# TGCC-HC-1_RF_Module.net
KiCad netlist of a schematic drawn in Altium Designer
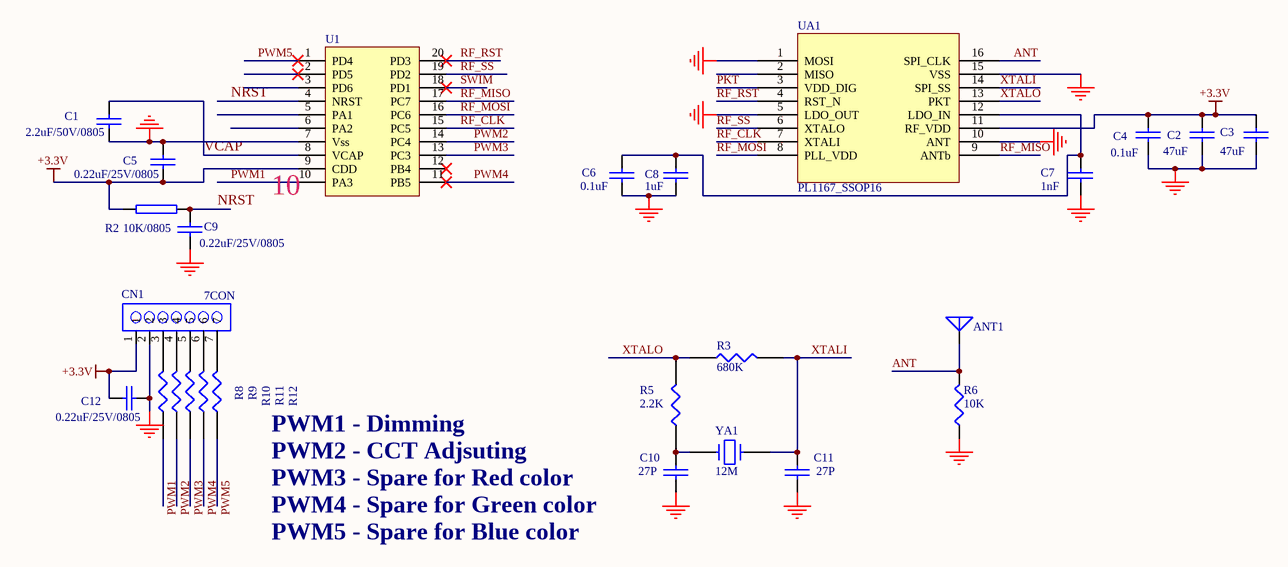
[diagram p0: TGCC-HC-1 RF Module.SchDoc]

(export (version "E")
  (design (tool "Eeschema 10.0.6"))
  (components
    (comp (ref "ANT1") (value "~") (description "Generic Antenna") (libsource (lib "*") (part "ANTENNA")))
    (comp (ref "C1") (value "2.2uF/50V/0805") (footprint "0402") (libsource (lib "") (part "CAP_1")))
    (comp (ref "C2")
      (value "47uF")
      (footprint "0402")
      (description "Capacitor")
      (libsource (lib "*") (part "CAP"))
    )
    (comp (ref "C3")
      (value "47uF")
      (footprint "0402")
      (description "Capacitor")
      (libsource (lib "*") (part "CAP"))
    )
    (comp (ref "C4")
      (value "0.1uF")
      (footprint "0402")
      (description "Capacitor")
      (libsource (lib "*") (part "CAP"))
    )
    (comp (ref "C5") (value "0.22uF/25V/0805") (footprint "0402") (libsource (lib "") (part "CAP_1")))
    (comp (ref "C6")
      (value "0.1uF")
      (footprint "0402")
      (description "Capacitor")
      (libsource (lib "*") (part "CAP"))
    )
    (comp (ref "C7")
      (value "1nF")
      (footprint "0402")
      (description "Capacitor")
      (libsource (lib "*") (part "CAP"))
    )
    (comp (ref "C8")
      (value "1uF")
      (footprint "0402")
      (description "Capacitor")
      (libsource (lib "*") (part "CAP"))
    )
    (comp (ref "C9") (value "0.22uF/25V/0805") (footprint "0402") (libsource (lib "") (part "CAP_1")))
    (comp (ref "C10")
      (value "27P")
      (footprint "0402")
      (description "Capacitor")
      (libsource (lib "*") (part "CAP"))
    )
    (comp (ref "C11")
      (value "27P")
      (footprint "0402")
      (description "Capacitor")
      (libsource (lib "*") (part "CAP"))
    )
    (comp (ref "C12") (value "0.22uF/25V/0805") (footprint "0402") (libsource (lib "") (part "CAP_1")))
    (comp (ref "CN1") (value "7CON") (footprint "HDR1X7") (libsource (lib "钜景电子SCH") (part "7CON")))
    (comp (ref "R2")
      (value "10K/0805")
      (footprint "0402")
      (libsource (lib "Backup of anthonysch") (part "RES2"))
    )
    (comp (ref "R3") (value "680K") (footprint "0402") (libsource (lib "*") (part "RES1")))
    (comp (ref "R5") (value "2.2K") (footprint "0402") (libsource (lib "*") (part "RES1")))
    (comp (ref "R6") (value "10K") (footprint "0402") (libsource (lib "") (part "RES1_1")))
    (comp (ref "R8") (value "~") (footprint "0402") (libsource (lib "*") (part "RES1")))
    (comp (ref "R9") (value "~") (footprint "0402") (libsource (lib "*") (part "RES1")))
    (comp (ref "R10") (value "~") (footprint "0402") (libsource (lib "*") (part "RES1")))
    (comp (ref "R11") (value "~") (footprint "0402") (libsource (lib "*") (part "RES1")))
    (comp (ref "R12") (value "~") (footprint "0402") (libsource (lib "*") (part "RES1")))
    (comp (ref "U1") (value "~") (footprint "MCU") (libsource (lib "钜景电子SCH") (part "STM8S103")))
    (comp (ref "UA1") (value "PL1167_SSOP16") (footprint "SSOP-16") (libsource (lib "*") (part "CW1803")))
    (comp (ref "YA1")
      (value "12M")
      (footprint "XTAL-SMD")
      (description "Crystal")
      (libsource (lib "*") (part "CRYSTAL"))
    )
  )
  (nets
    (net (code "1") (name "+3.3V") (class "Default")
      (node (ref "C12") (pin "1") (pintype "passive"))
      (node (ref "C2") (pin "1") (pinfunction "1_1") (pintype "passive"))
      (node (ref "C3") (pin "1") (pinfunction "1_1") (pintype "passive"))
      (node (ref "C4") (pin "1") (pinfunction "1_1") (pintype "passive"))
      (node (ref "C5") (pin "2") (pintype "passive"))
      (node (ref "CN1") (pin "1") (pinfunction "1_1") (pintype "passive"))
      (node (ref "R2") (pin "2") (pintype "passive"))
      (node (ref "U1") (pin "9") (pinfunction "CDD_9") (pintype "power_in"))
      (node (ref "UA1") (pin "11") (pinfunction "RF_VDD_11") (pintype "passive"))
    )
    (net (code "2") (name "/ANT") (class "Default")
      (node (ref "ANT1") (pin "1") (pinfunction "A_1") (pintype "passive"))
      (node (ref "R6") (pin "2") (pinfunction "2_2") (pintype "passive"))
      (node (ref "UA1") (pin "16") (pinfunction "SPI_CLK_16") (pintype "passive"))
    )
    (net (code "3") (name "/NRST") (class "Default")
      (node (ref "C9") (pin "1") (pintype "passive"))
      (node (ref "R2") (pin "1") (pintype "passive"))
      (node (ref "U1") (pin "4") (pinfunction "NRST_4") (pintype "power_in"))
    )
    (net (code "4") (name "/PKT") (class "Default")
      (node (ref "UA1") (pin "3") (pinfunction "VDD_DIG_3") (pintype "passive"))
    )
    (net (code "5") (name "/PWM1") (class "Default")
      (node (ref "R8") (pin "1") (pinfunction "1_1") (pintype "passive"))
      (node (ref "U1") (pin "10") (pinfunction "PA3_10") (pintype "power_in"))
    )
    (net (code "6") (name "/PWM2") (class "Default")
      (node (ref "R9") (pin "1") (pinfunction "1_1") (pintype "passive"))
      (node (ref "U1") (pin "14") (pinfunction "PC4_14") (pintype "power_in"))
    )
    (net (code "7") (name "/PWM3") (class "Default")
      (node (ref "R10") (pin "1") (pinfunction "1_1") (pintype "passive"))
      (node (ref "U1") (pin "13") (pinfunction "PC3_13") (pintype "power_in"))
    )
    (net (code "8") (name "/PWM4") (class "Default")
      (node (ref "R11") (pin "1") (pinfunction "1_1") (pintype "passive"))
      (node (ref "U1") (pin "11") (pinfunction "PB5_11") (pintype "power_in"))
    )
    (net (code "9") (name "/PWM5") (class "Default")
      (node (ref "R12") (pin "1") (pinfunction "1_1") (pintype "passive"))
      (node (ref "U1") (pin "1") (pinfunction "PD4_1") (pintype "power_in"))
    )
    (net (code "10") (name "/RF_CLK") (class "Default")
      (node (ref "U1") (pin "15") (pinfunction "PC5_15") (pintype "power_in"))
      (node (ref "UA1") (pin "7") (pinfunction "XTALI_7") (pintype "passive"))
    )
    (net (code "11") (name "/RF_MISO") (class "Default")
      (node (ref "U1") (pin "17") (pinfunction "PC7_17") (pintype "power_in"))
      (node (ref "UA1") (pin "9") (pinfunction "ANTb_9") (pintype "passive"))
    )
    (net (code "12") (name "/RF_MOSI") (class "Default")
      (node (ref "U1") (pin "16") (pinfunction "PC6_16") (pintype "power_in"))
      (node (ref "UA1") (pin "8") (pinfunction "PLL_VDD_8") (pintype "passive"))
    )
    (net (code "13") (name "/RF_RST") (class "Default")
      (node (ref "U1") (pin "20") (pinfunction "PD3_20") (pintype "power_in"))
      (node (ref "UA1") (pin "4") (pinfunction "RST_N_4") (pintype "passive"))
    )
    (net (code "14") (name "/RF_SS") (class "Default")
      (node (ref "U1") (pin "19") (pinfunction "PD2_19") (pintype "power_in"))
      (node (ref "UA1") (pin "6") (pinfunction "XTALO_6") (pintype "passive"))
    )
    (net (code "15") (name "/SWIM") (class "Default")
      (node (ref "U1") (pin "18") (pinfunction "PD1_18") (pintype "power_in+no_connect"))
    )
    (net (code "16") (name "/VCAP") (class "Default")
      (node (ref "C1") (pin "1") (pintype "passive"))
      (node (ref "U1") (pin "8") (pinfunction "VCAP_8") (pintype "power_in"))
    )
    (net (code "17") (name "/XTALI") (class "Default")
      (node (ref "C11") (pin "1") (pinfunction "1_1") (pintype "passive"))
      (node (ref "R3") (pin "2") (pinfunction "2_2") (pintype "passive"))
      (node (ref "UA1") (pin "14") (pinfunction "SPI_SS_14") (pintype "passive"))
      (node (ref "YA1") (pin "2") (pinfunction "2_2") (pintype "passive"))
    )
    (net (code "18") (name "/XTALO") (class "Default")
      (node (ref "R3") (pin "1") (pinfunction "1_1") (pintype "passive"))
      (node (ref "R5") (pin "2") (pinfunction "2_2") (pintype "passive"))
      (node (ref "UA1") (pin "13") (pinfunction "PKT_13") (pintype "passive"))
    )
    (net (code "19") (name "GND") (class "Default")
      (node (ref "C1") (pin "2") (pintype "passive"))
      (node (ref "C10") (pin "2") (pinfunction "2_2") (pintype "passive"))
      (node (ref "C11") (pin "2") (pinfunction "2_2") (pintype "passive"))
      (node (ref "C12") (pin "2") (pintype "passive"))
      (node (ref "C2") (pin "2") (pinfunction "2_2") (pintype "passive"))
      (node (ref "C3") (pin "2") (pinfunction "2_2") (pintype "passive"))
      (node (ref "C4") (pin "2") (pinfunction "2_2") (pintype "passive"))
      (node (ref "C5") (pin "1") (pintype "passive"))
      (node (ref "C6") (pin "2") (pinfunction "2_2") (pintype "passive"))
      (node (ref "C7") (pin "2") (pinfunction "2_2") (pintype "passive"))
      (node (ref "C8") (pin "2") (pinfunction "2_2") (pintype "passive"))
      (node (ref "C9") (pin "2") (pintype "passive"))
      (node (ref "CN1") (pin "2") (pinfunction "2_2") (pintype "passive"))
      (node (ref "R6") (pin "1") (pinfunction "1_1") (pintype "passive"))
      (node (ref "U1") (pin "7") (pinfunction "Vss_7") (pintype "power_in"))
      (node (ref "UA1") (pin "1") (pinfunction "MOSI_1") (pintype "passive"))
      (node (ref "UA1") (pin "10") (pinfunction "ANT_10") (pintype "passive"))
      (node (ref "UA1") (pin "15") (pinfunction "VSS_15") (pintype "passive"))
      (node (ref "UA1") (pin "5") (pinfunction "LDO_OUT_5") (pintype "passive"))
    )
    (net (code "20") (name "Net-(C10-Pad1)") (class "Default")
      (node (ref "C10") (pin "1") (pinfunction "1_1") (pintype "passive"))
      (node (ref "R5") (pin "1") (pinfunction "1_1") (pintype "passive"))
      (node (ref "YA1") (pin "1") (pinfunction "1_1") (pintype "passive"))
    )
    (net (code "21") (name "Net-(CN1-Pad3)") (class "Default")
      (node (ref "CN1") (pin "3") (pinfunction "3_3") (pintype "passive"))
      (node (ref "R8") (pin "2") (pinfunction "2_2") (pintype "passive"))
    )
    (net (code "22") (name "Net-(CN1-Pad4)") (class "Default")
      (node (ref "CN1") (pin "4") (pinfunction "4_4") (pintype "passive"))
      (node (ref "R9") (pin "2") (pinfunction "2_2") (pintype "passive"))
    )
    (net (code "23") (name "Net-(CN1-Pad5)") (class "Default")
      (node (ref "CN1") (pin "5") (pinfunction "5_5") (pintype "passive"))
      (node (ref "R10") (pin "2") (pinfunction "2_2") (pintype "passive"))
    )
    (net (code "24") (name "Net-(CN1-Pad6)") (class "Default")
      (node (ref "CN1") (pin "6") (pinfunction "6_6") (pintype "passive"))
      (node (ref "R11") (pin "2") (pinfunction "2_2") (pintype "passive"))
    )
    (net (code "25") (name "Net-(CN1-Pad7)") (class "Default")
      (node (ref "CN1") (pin "7") (pinfunction "7_7") (pintype "passive"))
      (node (ref "R12") (pin "2") (pinfunction "2_2") (pintype "passive"))
    )
    (net (code "26") (name "Net-(UA1-LDO_IN)") (class "Default")
      (node (ref "C6") (pin "1") (pinfunction "1_1") (pintype "passive"))
      (node (ref "C7") (pin "1") (pinfunction "1_1") (pintype "passive"))
      (node (ref "C8") (pin "1") (pinfunction "1_1") (pintype "passive"))
      (node (ref "UA1") (pin "12") (pinfunction "LDO_IN_12") (pintype "passive"))
    )
    (net (code "27") (name "unconnected-(U1-PA1-Pad5)") (class "Default")
      (node (ref "U1") (pin "5") (pinfunction "PA1_5") (pintype "power_in"))
    )
    (net (code "28") (name "unconnected-(U1-PA2-Pad6)") (class "Default")
      (node (ref "U1") (pin "6") (pinfunction "PA2_6") (pintype "power_in"))
    )
    (net (code "29") (name "unconnected-(U1-PB4-Pad12)") (class "Default")
      (node (ref "U1") (pin "12") (pinfunction "PB4_12") (pintype "power_in+no_connect"))
    )
    (net (code "30") (name "unconnected-(U1-PD5-Pad2)") (class "Default")
      (node (ref "U1") (pin "2") (pinfunction "PD5_2") (pintype "power_in+no_connect"))
    )
    (net (code "31") (name "unconnected-(U1-PD6-Pad3)") (class "Default")
      (node (ref "U1") (pin "3") (pinfunction "PD6_3") (pintype "power_in"))
    )
    (net (code "32") (name "unconnected-(UA1-MISO-Pad2)") (class "Default")
      (node (ref "UA1") (pin "2") (pinfunction "MISO_2") (pintype "passive"))
    )
  )
)
